# PCB_Roomba.net
KiCad netlist of a schematic drawn in Altium Designer
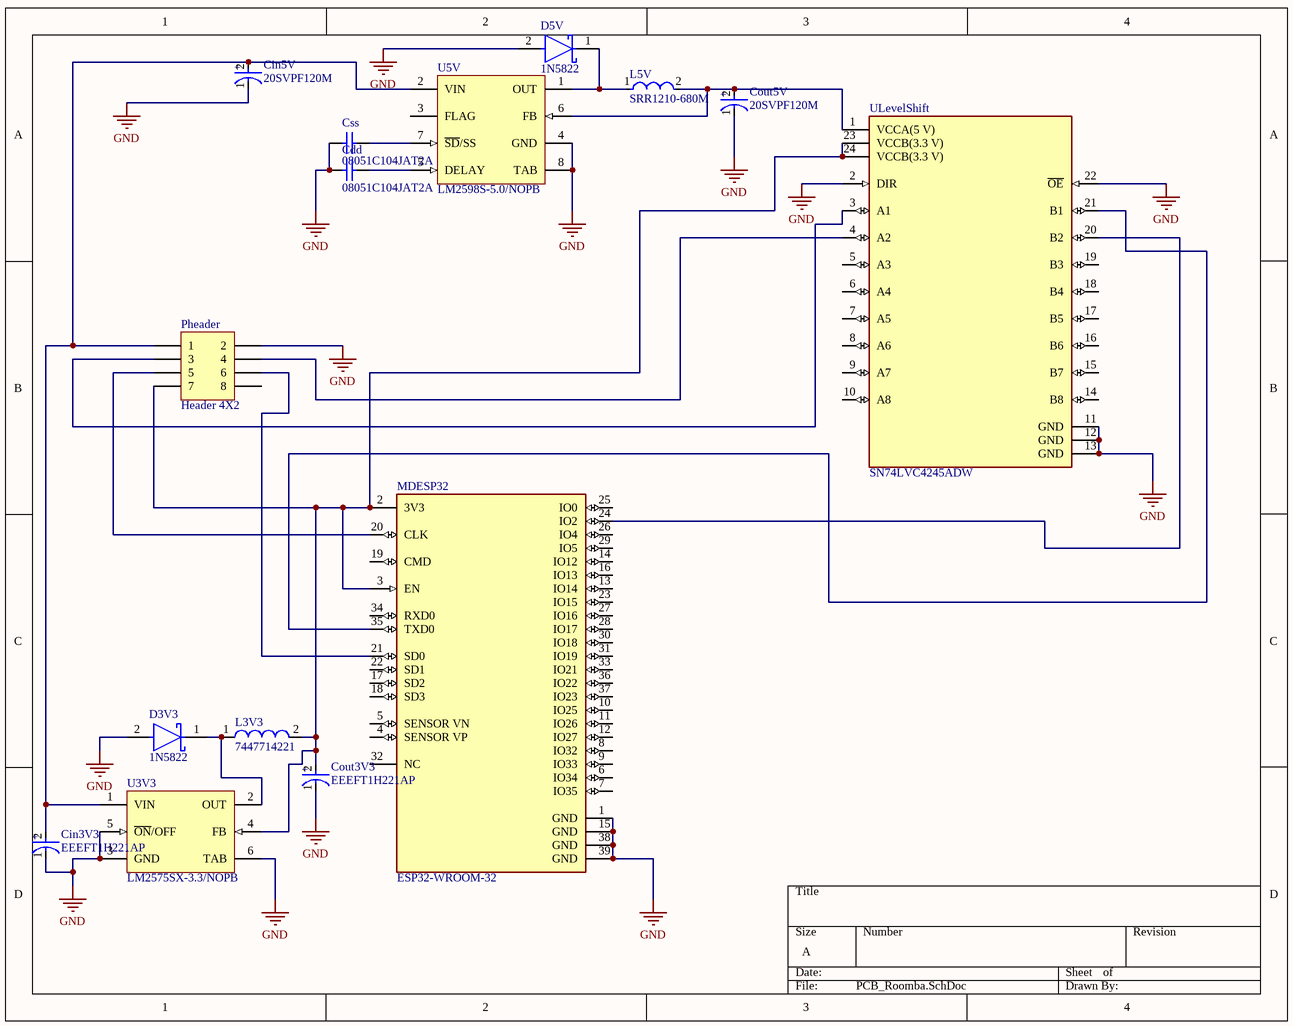
[diagram p0: PCB_Roomba.SchDoc]

(export (version "E")
  (design (tool "Eeschema 10.0.6"))
  (components
    (comp (ref "Cdd")
      (value "08051C104JAT2A")
      (footprint "CAPC2013X94X50ML20T25")
      (fields (field (name "MANUFACTURER") "AVX Interconnect / Elco"))
      (libsource (lib "Altium Content Vault") (part "CAP"))
    )
    (comp (ref "Cin3V3")
      (value "EEEFT1H221AP")
      (footprint "FP-FTF-MFG")
      (description "CAP ALUM 220UF 20% 50V SMD")
      (fields (field (name "TOLERANCE") "20%") (field (name "VOLTAGE") "50V"))
      (libsource (lib "Altium Content Vault") (part "203bc49f2ac43e59fd269a8c329ed05"))
    )
    (comp (ref "Cin5V")
      (value "20SVPF120M")
      (footprint "FP-OS-CON-SMT-C6-MFG")
      (description "Conductive Polymer Aluminum Solid Capacitors (OS-CON) 120uF ±20% 20V")
      (fields (field (name "TOLERANCE") "20%") (field (name "VOLTAGE") "20V"))
      (libsource (lib "Altium Content Vault") (part "a00bbbee19879c290e62620ae7e47b1"))
    )
    (comp (ref "Cout3V3")
      (value "EEEFT1H221AP")
      (footprint "FP-FTF-MFG")
      (description "CAP ALUM 220UF 20% 50V SMD")
      (fields (field (name "TOLERANCE") "20%") (field (name "VOLTAGE") "50V"))
      (libsource (lib "Altium Content Vault") (part "203bc49f2ac43e59fd269a8c329ed05"))
    )
    (comp (ref "Cout5V")
      (value "20SVPF120M")
      (footprint "FP-OS-CON-SMT-C6-MFG")
      (description "Conductive Polymer Aluminum Solid Capacitors (OS-CON) 120uF ±20% 20V")
      (fields (field (name "TOLERANCE") "20%") (field (name "VOLTAGE") "20V"))
      (libsource (lib "Altium Content Vault") (part "a00bbbee19879c290e62620ae7e47b1"))
    )
    (comp (ref "Css")
      (value "08051C104JAT2A")
      (footprint "CAPC2013X94X50ML20T25")
      (fields (field (name "MANUFACTURER") "AVX Interconnect / Elco"))
      (libsource (lib "Altium Content Vault") (part "CAP"))
    )
    (comp (ref "D3V3")
      (value "1N5822")
      (footprint "FP-DO-201AD-MFG")
      (description "DIODE SCHOTTKY 40V 3A DO201AD")
      (fields
        (field (name "OCTOPART") "https://octopart.com/1n5822-stmicroelectronics-323225")
        (field (name "MANUFACTURER") "STMicroelectronics")
      )
      (libsource (lib "Altium Content Vault") (part "1d6ec82d83fb6aee721767c19dac4b9"))
    )
    (comp (ref "D5V")
      (value "1N5822")
      (footprint "FP-DO-201AD-MFG")
      (description "DIODE SCHOTTKY 40V 3A DO201AD")
      (fields
        (field (name "OCTOPART") "https://octopart.com/1n5822-stmicroelectronics-323225")
        (field (name "MANUFACTURER") "STMicroelectronics")
      )
      (libsource (lib "Altium Content Vault") (part "1d6ec82d83fb6aee721767c19dac4b9"))
    )
    (comp (ref "L3V3")
      (value "7447714221")
      (footprint "WE-PD 1050")
      (description "SMD-Shielded Power Inductor WE-PD, L=220 µH")
      (fields (field (name "MANUFACTURER") "Wuerth Elektronik"))
      (libsource (lib "Altium Content Vault") (part "PAS-IND-INDUCTOR-2"))
    )
    (comp (ref "L5V")
      (value "SRR1210-680M")
      (footprint "FP-SRR1210-MFG")
      (description "FIXED IND 68UH 3A 102 MOHM SMD")
      (fields (field (name "TOLERANCE") "20%") (field (name "MANUFACTURER") "Bourns"))
      (libsource (lib "Altium Content Vault") (part "725321dda6339637d4d059423bc1c3c"))
    )
    (comp (ref "MDESP32")
      (value "ESP32-WROOM-32")
      (footprint "FP-ESP32-WROOM-32-MFG")
      (description "RX TXRX MOD WIFI SURFACE MOUNT")
      (libsource (lib "Altium Content Vault") (part "ee866abf0b6c51247b7f5cdebf2f250"))
    )
    (comp (ref "Pheader")
      (value "Header 4X2")
      (footprint "HDR2X4")
      (description "Header, 4-Pin, Dual row")
      (fields (field (name "PUBLISHER") "Altium Limited"))
      (libsource (lib "Miscellaneous Connectors") (part "Header 4X2"))
    )
    (comp (ref "U3V3")
      (value "LM2575SX-3.3/NOPB")
      (footprint "KTT0005B_L")
      (description "SIMPLE SWITCHER® 1A Step-Down Voltage Regulator, 5-pin TO-263, Pb-Free")
      (fields (field (name "MANUFACTURER") "Texas Instruments"))
      (libsource (lib "Altium Content Vault") (part "PM-REG-LM2575HVS-12"))
    )
    (comp (ref "U5V")
      (value "LM2598S-5.0/NOPB")
      (footprint "KTW0007B_N")
      (fields (field (name "MANUFACTURER") "Texas Instruments"))
      (libsource (lib "Altium Content Vault") (part "PM-REG-LM2598S-12"))
    )
    (comp (ref "ULevelShift")
      (value "SN74LVC4245ADW")
      (footprint "FP-DW0024A-MFG")
      (description "IC TRNSLTR BIDIRECTIONAL 24SOIC")
      (libsource (lib "Altium Content Vault") (part "d0d23257eeaf0dffc47eb08469a374c"))
    )
  )
  (nets
    (net (code "1") (name "GND") (class "Default")
      (node (ref "Cdd") (pin "1") (pinfunction "1_1") (pintype "passive"))
      (node (ref "Cin3V3") (pin "1") (pinfunction "C_1") (pintype "passive"))
      (node (ref "Cin5V") (pin "1") (pinfunction "C_1") (pintype "passive"))
      (node (ref "Cout3V3") (pin "1") (pinfunction "C_1") (pintype "passive"))
      (node (ref "Cout5V") (pin "1") (pinfunction "C_1") (pintype "passive"))
      (node (ref "Css") (pin "1") (pinfunction "1_1") (pintype "passive"))
      (node (ref "D3V3") (pin "2") (pinfunction "A_2") (pintype "passive"))
      (node (ref "D5V") (pin "2") (pinfunction "A_2") (pintype "passive"))
      (node (ref "MDESP32") (pin "1") (pinfunction "GND_1") (pintype "power_in"))
      (node (ref "MDESP32") (pin "15") (pinfunction "GND_15") (pintype "power_in"))
      (node (ref "MDESP32") (pin "38") (pinfunction "GND_38") (pintype "power_in"))
      (node (ref "MDESP32") (pin "39") (pinfunction "GND_39") (pintype "power_in"))
      (node (ref "Pheader") (pin "2") (pinfunction "2_2") (pintype "passive"))
      (node (ref "U3V3") (pin "3") (pinfunction "GND_3") (pintype "power_in"))
      (node (ref "U3V3") (pin "5") (pinfunction "~{ON}/OFF_5") (pintype "input"))
      (node (ref "U3V3") (pin "6") (pinfunction "TAB_6") (pintype "power_in"))
      (node (ref "U5V") (pin "4") (pinfunction "GND_4") (pintype "power_in"))
      (node (ref "U5V") (pin "8") (pinfunction "TAB_8") (pintype "power_in"))
      (node (ref "ULevelShift") (pin "11") (pinfunction "GND_11") (pintype "power_in"))
      (node (ref "ULevelShift") (pin "12") (pinfunction "GND_12") (pintype "power_in"))
      (node (ref "ULevelShift") (pin "13") (pinfunction "GND_13") (pintype "power_in"))
      (node (ref "ULevelShift") (pin "2") (pinfunction "DIR_2") (pintype "input"))
      (node (ref "ULevelShift") (pin "22") (pinfunction "~{OE}_22") (pintype "input"))
    )
    (net (code "2") (name "Net-(Cin3V3-A)") (class "Default")
      (node (ref "Cin3V3") (pin "2") (pinfunction "A_2") (pintype "passive"))
      (node (ref "Cin5V") (pin "2") (pinfunction "A_2") (pintype "passive"))
      (node (ref "Pheader") (pin "1") (pinfunction "1_1") (pintype "passive"))
      (node (ref "U3V3") (pin "1") (pinfunction "VIN_1") (pintype "power_in"))
      (node (ref "U5V") (pin "2") (pinfunction "VIN_2") (pintype "power_in"))
    )
    (net (code "3") (name "Net-(Cout3V3-A)") (class "Default")
      (node (ref "Cout3V3") (pin "2") (pinfunction "A_2") (pintype "passive"))
      (node (ref "L3V3") (pin "2") (pinfunction "2_2") (pintype "passive"))
      (node (ref "MDESP32") (pin "2") (pinfunction "3V3_2") (pintype "power_in"))
      (node (ref "MDESP32") (pin "3") (pinfunction "EN_3") (pintype "input"))
      (node (ref "Pheader") (pin "7") (pinfunction "7_7") (pintype "passive"))
      (node (ref "U3V3") (pin "4") (pinfunction "FB_4") (pintype "input"))
      (node (ref "ULevelShift") (pin "23") (pinfunction "VCCB(3.3_V)_23") (pintype "power_in"))
      (node (ref "ULevelShift") (pin "24") (pinfunction "VCCB(3.3_V)_24") (pintype "power_in"))
    )
    (net (code "4") (name "Net-(Cout5V-A)") (class "Default")
      (node (ref "Cout5V") (pin "2") (pinfunction "A_2") (pintype "passive"))
      (node (ref "L5V") (pin "2") (pinfunction "2_2") (pintype "passive"))
      (node (ref "U5V") (pin "6") (pinfunction "FB_6") (pintype "input"))
      (node (ref "ULevelShift") (pin "1") (pinfunction "VCCA(5_V)_1") (pintype "power_in"))
    )
    (net (code "5") (name "Net-(D3V3-C)") (class "Default")
      (node (ref "D3V3") (pin "1") (pinfunction "C_1") (pintype "passive"))
      (node (ref "L3V3") (pin "1") (pinfunction "1_1") (pintype "passive"))
      (node (ref "U3V3") (pin "2") (pinfunction "OUT_2") (pintype "power_in"))
    )
    (net (code "6") (name "Net-(D5V-C)") (class "Default")
      (node (ref "D5V") (pin "1") (pinfunction "C_1") (pintype "passive"))
      (node (ref "L5V") (pin "1") (pinfunction "1_1") (pintype "passive"))
      (node (ref "U5V") (pin "1") (pinfunction "OUT_1") (pintype "power_in"))
    )
    (net (code "7") (name "Net-(MDESP32-CLK)") (class "Default")
      (node (ref "MDESP32") (pin "20") (pinfunction "CLK_20") (pintype "bidirectional"))
      (node (ref "Pheader") (pin "5") (pinfunction "5_5") (pintype "passive"))
    )
    (net (code "8") (name "Net-(MDESP32-IO2)") (class "Default")
      (node (ref "MDESP32") (pin "24") (pinfunction "IO2_24") (pintype "bidirectional"))
      (node (ref "ULevelShift") (pin "20") (pinfunction "B2_20") (pintype "bidirectional"))
    )
    (net (code "9") (name "Net-(MDESP32-SD0)") (class "Default")
      (node (ref "MDESP32") (pin "21") (pinfunction "SD0_21") (pintype "bidirectional"))
      (node (ref "Pheader") (pin "6") (pinfunction "6_6") (pintype "passive"))
    )
    (net (code "10") (name "Net-(MDESP32-TXD0)") (class "Default")
      (node (ref "MDESP32") (pin "35") (pinfunction "TXD0_35") (pintype "bidirectional"))
      (node (ref "ULevelShift") (pin "21") (pinfunction "B1_21") (pintype "bidirectional"))
    )
    (net (code "11") (name "Net-(U5V-DELAY)") (class "Default")
      (node (ref "Cdd") (pin "2") (pinfunction "2_2") (pintype "passive"))
      (node (ref "U5V") (pin "5") (pinfunction "DELAY_5") (pintype "input"))
    )
    (net (code "12") (name "Net-(U5V-~{SD}{slash}SS)") (class "Default")
      (node (ref "Css") (pin "2") (pinfunction "2_2") (pintype "passive"))
      (node (ref "U5V") (pin "7") (pinfunction "~{SD}/SS_7") (pintype "input"))
    )
    (net (code "13") (name "Net-(ULevelShift-A1)") (class "Default")
      (node (ref "Pheader") (pin "3") (pinfunction "3_3") (pintype "passive"))
      (node (ref "ULevelShift") (pin "3") (pinfunction "A1_3") (pintype "bidirectional"))
    )
    (net (code "14") (name "Net-(ULevelShift-A2)") (class "Default")
      (node (ref "Pheader") (pin "4") (pinfunction "4_4") (pintype "passive"))
      (node (ref "ULevelShift") (pin "4") (pinfunction "A2_4") (pintype "bidirectional"))
    )
    (net (code "15") (name "unconnected-(MDESP32-CMD-Pad19)") (class "Default")
      (node (ref "MDESP32") (pin "19") (pinfunction "CMD_19") (pintype "bidirectional"))
    )
    (net (code "16") (name "unconnected-(MDESP32-IO0-Pad25)") (class "Default")
      (node (ref "MDESP32") (pin "25") (pinfunction "IO0_25") (pintype "bidirectional"))
    )
    (net (code "17") (name "unconnected-(MDESP32-IO4-Pad26)") (class "Default")
      (node (ref "MDESP32") (pin "26") (pinfunction "IO4_26") (pintype "bidirectional"))
    )
    (net (code "18") (name "unconnected-(MDESP32-IO5-Pad29)") (class "Default")
      (node (ref "MDESP32") (pin "29") (pinfunction "IO5_29") (pintype "bidirectional"))
    )
    (net (code "19") (name "unconnected-(MDESP32-IO12-Pad14)") (class "Default")
      (node (ref "MDESP32") (pin "14") (pinfunction "IO12_14") (pintype "bidirectional"))
    )
    (net (code "20") (name "unconnected-(MDESP32-IO13-Pad16)") (class "Default")
      (node (ref "MDESP32") (pin "16") (pinfunction "IO13_16") (pintype "bidirectional"))
    )
    (net (code "21") (name "unconnected-(MDESP32-IO14-Pad13)") (class "Default")
      (node (ref "MDESP32") (pin "13") (pinfunction "IO14_13") (pintype "bidirectional"))
    )
    (net (code "22") (name "unconnected-(MDESP32-IO15-Pad23)") (class "Default")
      (node (ref "MDESP32") (pin "23") (pinfunction "IO15_23") (pintype "bidirectional"))
    )
    (net (code "23") (name "unconnected-(MDESP32-IO16-Pad27)") (class "Default")
      (node (ref "MDESP32") (pin "27") (pinfunction "IO16_27") (pintype "bidirectional"))
    )
    (net (code "24") (name "unconnected-(MDESP32-IO17-Pad28)") (class "Default")
      (node (ref "MDESP32") (pin "28") (pinfunction "IO17_28") (pintype "bidirectional"))
    )
    (net (code "25") (name "unconnected-(MDESP32-IO18-Pad30)") (class "Default")
      (node (ref "MDESP32") (pin "30") (pinfunction "IO18_30") (pintype "bidirectional"))
    )
    (net (code "26") (name "unconnected-(MDESP32-IO19-Pad31)") (class "Default")
      (node (ref "MDESP32") (pin "31") (pinfunction "IO19_31") (pintype "bidirectional"))
    )
    (net (code "27") (name "unconnected-(MDESP32-IO21-Pad33)") (class "Default")
      (node (ref "MDESP32") (pin "33") (pinfunction "IO21_33") (pintype "bidirectional"))
    )
    (net (code "28") (name "unconnected-(MDESP32-IO22-Pad36)") (class "Default")
      (node (ref "MDESP32") (pin "36") (pinfunction "IO22_36") (pintype "bidirectional"))
    )
    (net (code "29") (name "unconnected-(MDESP32-IO23-Pad37)") (class "Default")
      (node (ref "MDESP32") (pin "37") (pinfunction "IO23_37") (pintype "bidirectional"))
    )
    (net (code "30") (name "unconnected-(MDESP32-IO25-Pad10)") (class "Default")
      (node (ref "MDESP32") (pin "10") (pinfunction "IO25_10") (pintype "bidirectional"))
    )
    (net (code "31") (name "unconnected-(MDESP32-IO26-Pad11)") (class "Default")
      (node (ref "MDESP32") (pin "11") (pinfunction "IO26_11") (pintype "bidirectional"))
    )
    (net (code "32") (name "unconnected-(MDESP32-IO27-Pad12)") (class "Default")
      (node (ref "MDESP32") (pin "12") (pinfunction "IO27_12") (pintype "bidirectional"))
    )
    (net (code "33") (name "unconnected-(MDESP32-IO32-Pad8)") (class "Default")
      (node (ref "MDESP32") (pin "8") (pinfunction "IO32_8") (pintype "bidirectional"))
    )
    (net (code "34") (name "unconnected-(MDESP32-IO33-Pad9)") (class "Default")
      (node (ref "MDESP32") (pin "9") (pinfunction "IO33_9") (pintype "bidirectional"))
    )
    (net (code "35") (name "unconnected-(MDESP32-IO34-Pad6)") (class "Default")
      (node (ref "MDESP32") (pin "6") (pinfunction "IO34_6") (pintype "bidirectional"))
    )
    (net (code "36") (name "unconnected-(MDESP32-IO35-Pad7)") (class "Default")
      (node (ref "MDESP32") (pin "7") (pinfunction "IO35_7") (pintype "bidirectional"))
    )
    (net (code "37") (name "unconnected-(MDESP32-NC-Pad32)") (class "Default")
      (node (ref "MDESP32") (pin "32") (pinfunction "NC_32") (pintype "passive"))
    )
    (net (code "38") (name "unconnected-(MDESP32-RXD0-Pad34)") (class "Default")
      (node (ref "MDESP32") (pin "34") (pinfunction "RXD0_34") (pintype "bidirectional"))
    )
    (net (code "39") (name "unconnected-(MDESP32-SD1-Pad22)") (class "Default")
      (node (ref "MDESP32") (pin "22") (pinfunction "SD1_22") (pintype "bidirectional"))
    )
    (net (code "40") (name "unconnected-(MDESP32-SD2-Pad17)") (class "Default")
      (node (ref "MDESP32") (pin "17") (pinfunction "SD2_17") (pintype "bidirectional"))
    )
    (net (code "41") (name "unconnected-(MDESP32-SD3-Pad18)") (class "Default")
      (node (ref "MDESP32") (pin "18") (pinfunction "SD3_18") (pintype "bidirectional"))
    )
    (net (code "42") (name "unconnected-(MDESP32-SENSOR_VN-Pad5)") (class "Default")
      (node (ref "MDESP32") (pin "5") (pinfunction "SENSOR_VN_5") (pintype "bidirectional"))
    )
    (net (code "43") (name "unconnected-(MDESP32-SENSOR_VP-Pad4)") (class "Default")
      (node (ref "MDESP32") (pin "4") (pinfunction "SENSOR_VP_4") (pintype "bidirectional"))
    )
    (net (code "44") (name "unconnected-(Pheader-Pad8)") (class "Default")
      (node (ref "Pheader") (pin "8") (pinfunction "8_8") (pintype "passive"))
    )
    (net (code "45") (name "unconnected-(U5V-FLAG-Pad3)") (class "Default")
      (node (ref "U5V") (pin "3") (pinfunction "FLAG_3") (pintype "open_collector"))
    )
    (net (code "46") (name "unconnected-(ULevelShift-A3-Pad5)") (class "Default")
      (node (ref "ULevelShift") (pin "5") (pinfunction "A3_5") (pintype "bidirectional"))
    )
    (net (code "47") (name "unconnected-(ULevelShift-A4-Pad6)") (class "Default")
      (node (ref "ULevelShift") (pin "6") (pinfunction "A4_6") (pintype "bidirectional"))
    )
    (net (code "48") (name "unconnected-(ULevelShift-A5-Pad7)") (class "Default")
      (node (ref "ULevelShift") (pin "7") (pinfunction "A5_7") (pintype "bidirectional"))
    )
    (net (code "49") (name "unconnected-(ULevelShift-A6-Pad8)") (class "Default")
      (node (ref "ULevelShift") (pin "8") (pinfunction "A6_8") (pintype "bidirectional"))
    )
    (net (code "50") (name "unconnected-(ULevelShift-A7-Pad9)") (class "Default")
      (node (ref "ULevelShift") (pin "9") (pinfunction "A7_9") (pintype "bidirectional"))
    )
    (net (code "51") (name "unconnected-(ULevelShift-A8-Pad10)") (class "Default")
      (node (ref "ULevelShift") (pin "10") (pinfunction "A8_10") (pintype "bidirectional"))
    )
    (net (code "52") (name "unconnected-(ULevelShift-B3-Pad19)") (class "Default")
      (node (ref "ULevelShift") (pin "19") (pinfunction "B3_19") (pintype "bidirectional"))
    )
    (net (code "53") (name "unconnected-(ULevelShift-B4-Pad18)") (class "Default")
      (node (ref "ULevelShift") (pin "18") (pinfunction "B4_18") (pintype "bidirectional"))
    )
    (net (code "54") (name "unconnected-(ULevelShift-B5-Pad17)") (class "Default")
      (node (ref "ULevelShift") (pin "17") (pinfunction "B5_17") (pintype "bidirectional"))
    )
    (net (code "55") (name "unconnected-(ULevelShift-B6-Pad16)") (class "Default")
      (node (ref "ULevelShift") (pin "16") (pinfunction "B6_16") (pintype "bidirectional"))
    )
    (net (code "56") (name "unconnected-(ULevelShift-B7-Pad15)") (class "Default")
      (node (ref "ULevelShift") (pin "15") (pinfunction "B7_15") (pintype "bidirectional"))
    )
    (net (code "57") (name "unconnected-(ULevelShift-B8-Pad14)") (class "Default")
      (node (ref "ULevelShift") (pin "14") (pinfunction "B8_14") (pintype "bidirectional"))
    )
  )
)
